# FPGA-7.net
KiCad netlist of a schematic drawn in Altium Designer
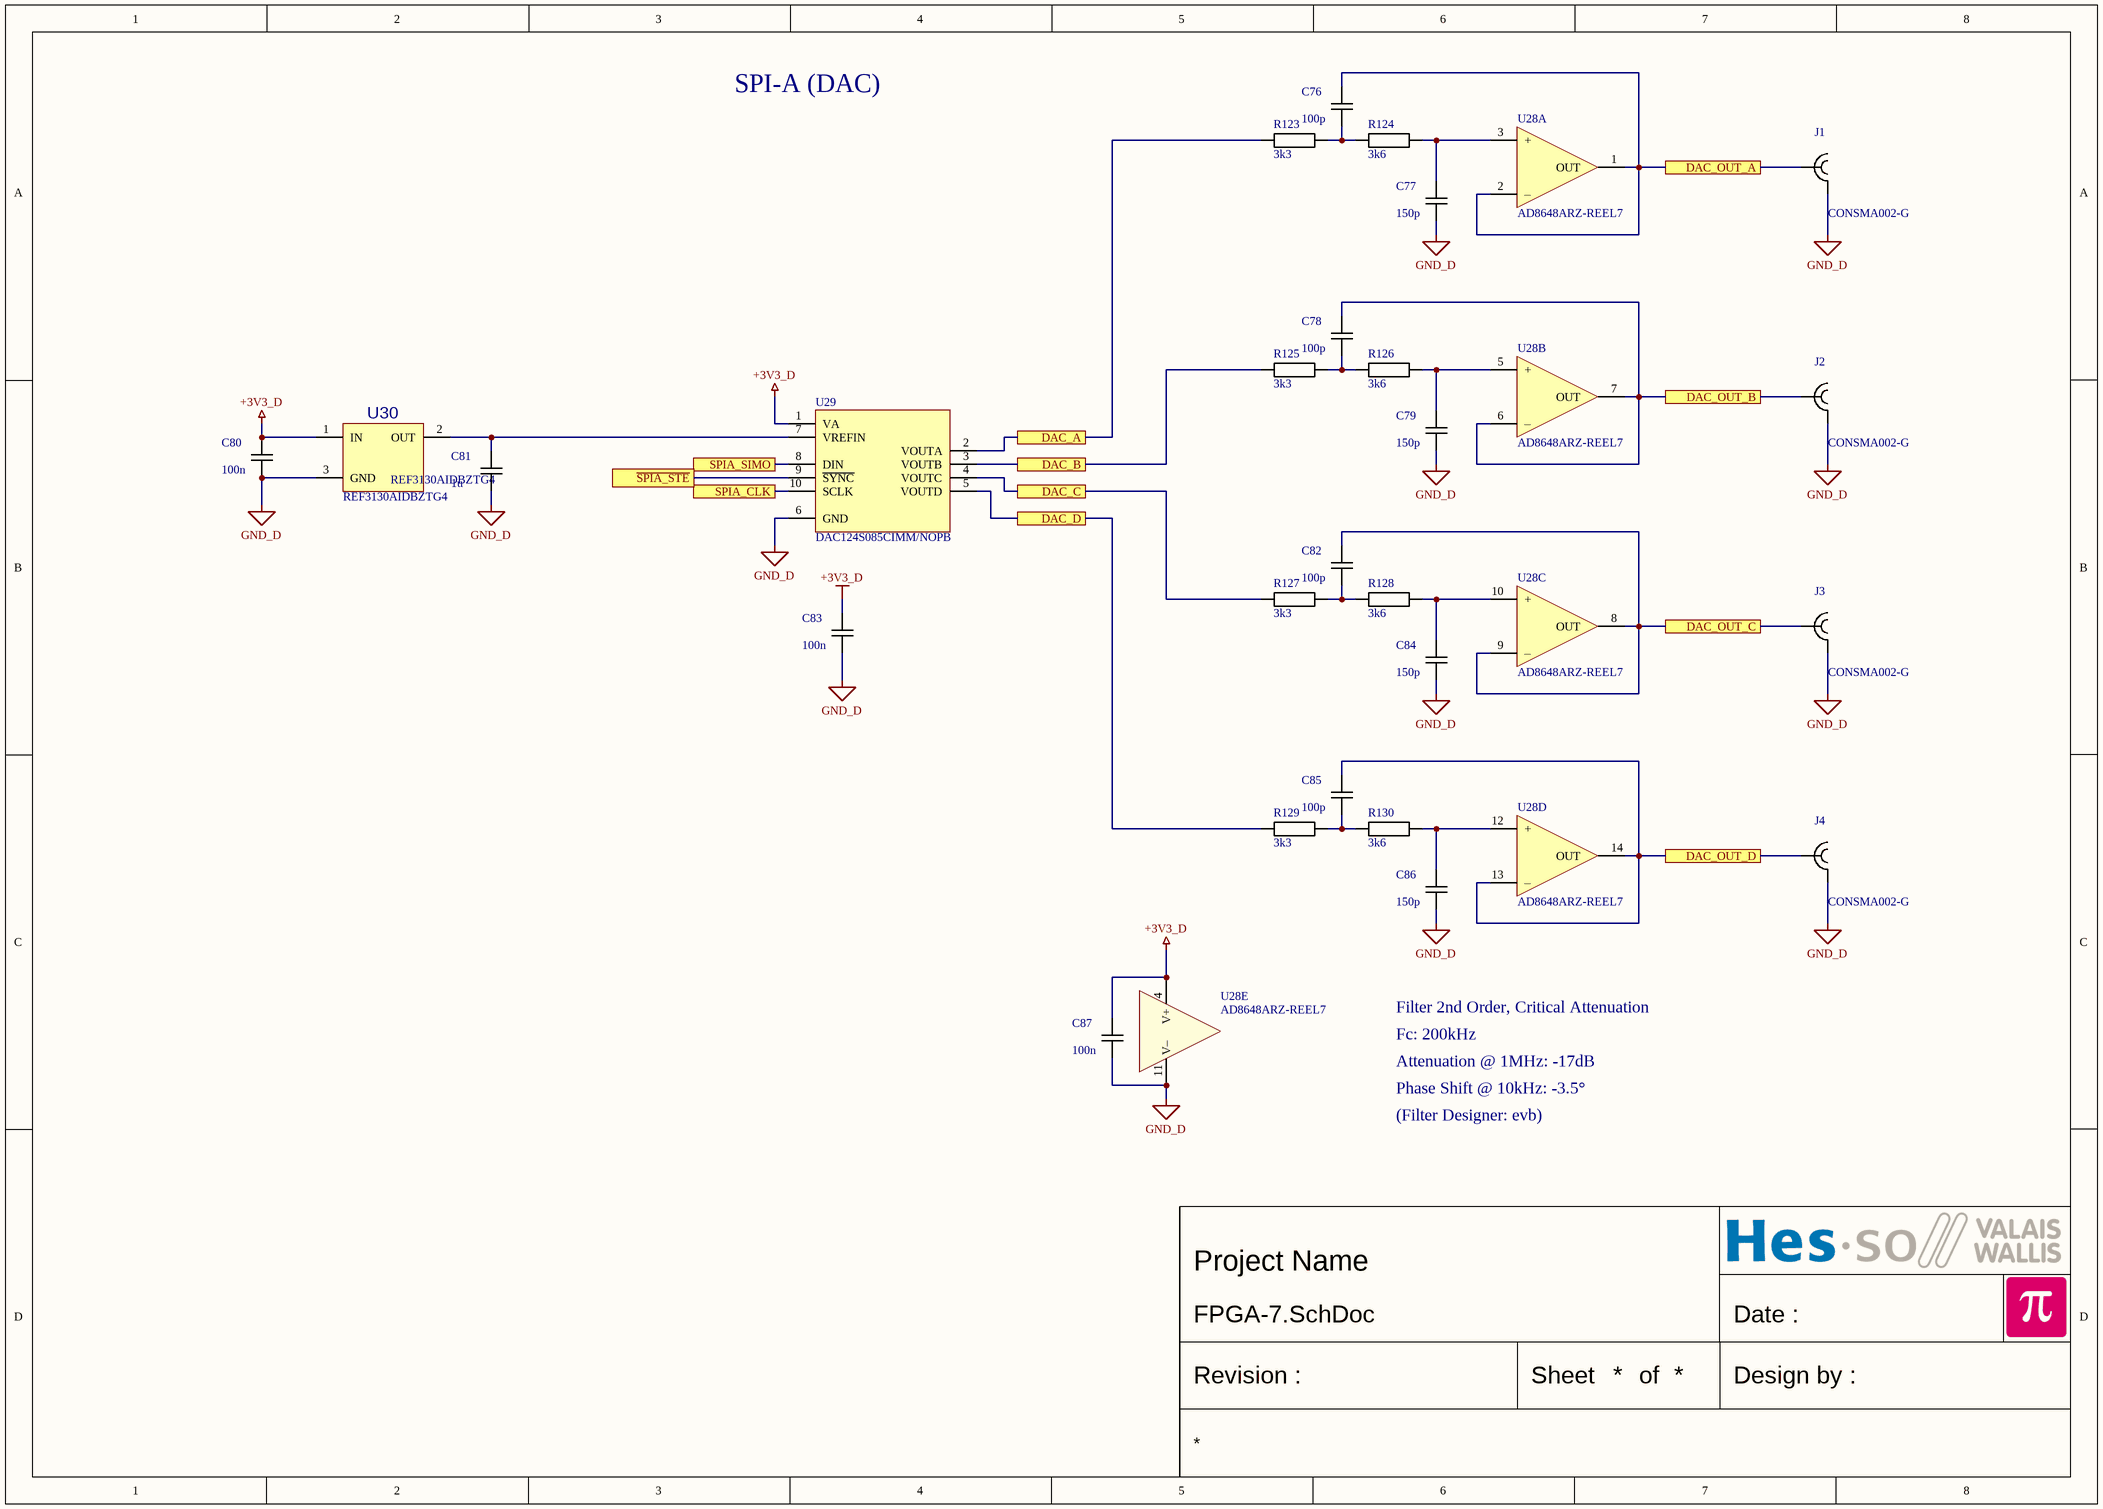
[diagram p0: FPGA-7.SchDoc]

(export (version "E")
  (design (tool "Eeschema 10.0.6"))
  (components
    (comp (ref "C76")
      (value "100p")
      (footprint "CAPACITOR 2012 REFLOW")
      (description "Capacitor X7R 10% 50V 2012(0805)")
      (libsource (lib "Capacitor") (part "Capacitor"))
    )
    (comp (ref "C77")
      (value "150p")
      (footprint "CAPACITOR 2012 REFLOW")
      (description "Capacitor X7R 10% 50V 2012(0805)")
      (libsource (lib "Capacitor") (part "Capacitor"))
    )
    (comp (ref "C78")
      (value "100p")
      (footprint "CAPACITOR 2012 REFLOW")
      (description "Capacitor X7R 10% 50V 2012(0805)")
      (libsource (lib "Capacitor") (part "Capacitor"))
    )
    (comp (ref "C79")
      (value "150p")
      (footprint "CAPACITOR 2012 REFLOW")
      (description "Capacitor X7R 10% 50V 2012(0805)")
      (libsource (lib "Capacitor") (part "Capacitor"))
    )
    (comp (ref "C80")
      (value "100n")
      (footprint "CAPACITOR 2012 REFLOW")
      (description "Capacitor X7R 10% 50V 2012(0805)")
      (libsource (lib "Capacitor") (part "Capacitor"))
    )
    (comp (ref "C81")
      (value "1u")
      (footprint "CAPACITOR 2012 REFLOW")
      (description "Capacitor X7R 10% 10V 2012(0805)")
      (libsource (lib "Capacitor") (part "Capacitor"))
    )
    (comp (ref "C82")
      (value "100p")
      (footprint "CAPACITOR 2012 REFLOW")
      (description "Capacitor X7R 10% 50V 2012(0805)")
      (libsource (lib "Capacitor") (part "Capacitor"))
    )
    (comp (ref "C83")
      (value "100n")
      (footprint "CAPACITOR 1608 REFLOW")
      (description "Capacitor X7R 10% 50V 1608(0603)")
      (libsource (lib "Capacitor") (part "Capacitor"))
    )
    (comp (ref "C84")
      (value "150p")
      (footprint "CAPACITOR 2012 REFLOW")
      (description "Capacitor X7R 10% 50V 2012(0805)")
      (libsource (lib "Capacitor") (part "Capacitor"))
    )
    (comp (ref "C85")
      (value "100p")
      (footprint "CAPACITOR 2012 REFLOW")
      (description "Capacitor X7R 10% 50V 2012(0805)")
      (libsource (lib "Capacitor") (part "Capacitor"))
    )
    (comp (ref "C86")
      (value "150p")
      (footprint "CAPACITOR 2012 REFLOW")
      (description "Capacitor X7R 10% 50V 2012(0805)")
      (libsource (lib "Capacitor") (part "Capacitor"))
    )
    (comp (ref "C87")
      (value "100n")
      (footprint "CAPACITOR 1608 REFLOW")
      (description "Capacitor X7R 10% 50V 1608(0603)")
      (libsource (lib "Capacitor") (part "Capacitor"))
    )
    (comp (ref "J1")
      (value "CONSMA002-G")
      (footprint "SMA TH Right Angle Linx CONSMA002")
      (description "SMA TH RIGHT ANGLE LINX CONSMA002")
      (fields (field (name "MANUFACTURER") "Linx Technologies"))
      (libsource (lib "Connector") (part "SMA TH RIGHT ANGLE LINX CONSMA002"))
    )
    (comp (ref "J2")
      (value "CONSMA002-G")
      (footprint "SMA TH Right Angle Linx CONSMA002")
      (description "SMA TH RIGHT ANGLE LINX CONSMA002")
      (fields (field (name "MANUFACTURER") "Linx Technologies"))
      (libsource (lib "Connector") (part "SMA TH RIGHT ANGLE LINX CONSMA002"))
    )
    (comp (ref "J3")
      (value "CONSMA002-G")
      (footprint "SMA TH Right Angle Linx CONSMA002")
      (description "SMA TH RIGHT ANGLE LINX CONSMA002")
      (fields (field (name "MANUFACTURER") "Linx Technologies"))
      (libsource (lib "Connector") (part "SMA TH RIGHT ANGLE LINX CONSMA002"))
    )
    (comp (ref "J4")
      (value "CONSMA002-G")
      (footprint "SMA TH Right Angle Linx CONSMA002")
      (description "SMA TH RIGHT ANGLE LINX CONSMA002")
      (fields (field (name "MANUFACTURER") "Linx Technologies"))
      (libsource (lib "Connector") (part "SMA TH RIGHT ANGLE LINX CONSMA002"))
    )
    (comp (ref "R123")
      (value "3k3")
      (footprint "RESISTOR 2012 REFLOW")
      (description "Resistor 1% 50V 125mW 2012(0805)")
      (libsource (lib "Resistor") (part "Resistor"))
    )
    (comp (ref "R124")
      (value "3k6")
      (footprint "RESISTOR 2012 REFLOW")
      (description "Resistor 1% 50V 125mW 2012(0805)")
      (libsource (lib "Resistor") (part "Resistor"))
    )
    (comp (ref "R125")
      (value "3k3")
      (footprint "RESISTOR 2012 REFLOW")
      (description "Resistor 1% 50V 125mW 2012(0805)")
      (libsource (lib "Resistor") (part "Resistor"))
    )
    (comp (ref "R126")
      (value "3k6")
      (footprint "RESISTOR 2012 REFLOW")
      (description "Resistor 1% 50V 125mW 2012(0805)")
      (libsource (lib "Resistor") (part "Resistor"))
    )
    (comp (ref "R127")
      (value "3k3")
      (footprint "RESISTOR 2012 REFLOW")
      (description "Resistor 1% 50V 125mW 2012(0805)")
      (libsource (lib "Resistor") (part "Resistor"))
    )
    (comp (ref "R128")
      (value "3k6")
      (footprint "RESISTOR 2012 REFLOW")
      (description "Resistor 1% 50V 125mW 2012(0805)")
      (libsource (lib "Resistor") (part "Resistor"))
    )
    (comp (ref "R129")
      (value "3k3")
      (footprint "RESISTOR 2012 REFLOW")
      (description "Resistor 1% 50V 125mW 2012(0805)")
      (libsource (lib "Resistor") (part "Resistor"))
    )
    (comp (ref "R130")
      (value "3k6")
      (footprint "RESISTOR 2012 REFLOW")
      (description "Resistor 1% 50V 125mW 2012(0805)")
      (libsource (lib "Resistor") (part "Resistor"))
    )
    (comp (ref "U28")
      (value "AD8648ARZ-REEL7")
      (footprint "SO14 P1.27 C4.0X8.8 H1.75")
      (description "Generic quad OPA 14 pins")
      (fields (field (name "MANUFACTURER") "Analog Devices"))
      (libsource (lib "Amplifier") (part "OPA QUAD"))
    )
    (comp (ref "U29")
      (value "DAC124S085CIMM/NOPB")
      (footprint "VSSOP10 P0.5 C3.1X3.1 H1.1")
      (description "DAC124S085 12-Bit Micro Power Quad Digital-to-Analog Converter With Rail-to-Rail Output")
      (fields (field (name "MANUFACTURER") "Texas Instruments"))
      (libsource (lib "Converter") (part "DAC124S085CIMM"))
    )
    (comp (ref "U30")
      (value "REF3130AIDBZTG4")
      (footprint "SOT23 P0.95 C1.6x3.0 H1.3")
      (description "Generic Positive Voltage Reference")
      (fields
        (field (name "ALTIUM_VALUE") "REF3130AIDBZTG4")
        (field (name "MANUFACTURER") "Texas Instruments")
      )
      (libsource (lib "Regulator") (part "REFERENCE SOT23 IN-OUT- GND"))
    )
  )
  (nets
    (net (code "1") (name "+3V3_D") (class "Default")
      (node (ref "C80") (pin "2") (pinfunction "2_2") (pintype "passive"))
      (node (ref "C83") (pin "2") (pinfunction "2_2") (pintype "passive"))
      (node (ref "C87") (pin "2") (pinfunction "2_2") (pintype "passive"))
      (node (ref "U28") (pin "4") (pinfunction "V+_4") (pintype "passive"))
      (node (ref "U29") (pin "1") (pinfunction "VA_1") (pintype "passive"))
      (node (ref "U30") (pin "1") (pinfunction "IN_1") (pintype "passive"))
    )
    (net (code "2") (name "/DAC_A") (class "Default")
      (node (ref "R123") (pin "1") (pinfunction "1_1") (pintype "passive"))
      (node (ref "U29") (pin "2") (pinfunction "VOUTA_2") (pintype "passive"))
    )
    (net (code "3") (name "/DAC_B") (class "Default")
      (node (ref "R125") (pin "1") (pinfunction "1_1") (pintype "passive"))
      (node (ref "U29") (pin "3") (pinfunction "VOUTB_3") (pintype "passive"))
    )
    (net (code "4") (name "/DAC_C") (class "Default")
      (node (ref "R127") (pin "1") (pinfunction "1_1") (pintype "passive"))
      (node (ref "U29") (pin "4") (pinfunction "VOUTC_4") (pintype "passive"))
    )
    (net (code "5") (name "/DAC_D") (class "Default")
      (node (ref "R129") (pin "1") (pinfunction "1_1") (pintype "passive"))
      (node (ref "U29") (pin "5") (pinfunction "VOUTD_5") (pintype "passive"))
    )
    (net (code "6") (name "/DAC_OUT_A") (class "Default")
      (node (ref "C76") (pin "2") (pinfunction "2_2") (pintype "passive"))
      (node (ref "J1") (pin "1") (pinfunction "1_1") (pintype "passive"))
      (node (ref "U28") (pin "1") (pinfunction "OUT_1") (pintype "passive"))
      (node (ref "U28") (pin "2") (pinfunction "–_2") (pintype "passive"))
    )
    (net (code "7") (name "/DAC_OUT_B") (class "Default")
      (node (ref "C78") (pin "2") (pinfunction "2_2") (pintype "passive"))
      (node (ref "J2") (pin "1") (pinfunction "1_1") (pintype "passive"))
      (node (ref "U28") (pin "6") (pinfunction "–_6") (pintype "passive"))
      (node (ref "U28") (pin "7") (pinfunction "OUT_7") (pintype "passive"))
    )
    (net (code "8") (name "/DAC_OUT_C") (class "Default")
      (node (ref "C82") (pin "2") (pinfunction "2_2") (pintype "passive"))
      (node (ref "J3") (pin "1") (pinfunction "1_1") (pintype "passive"))
      (node (ref "U28") (pin "8") (pinfunction "OUT_8") (pintype "passive"))
      (node (ref "U28") (pin "9") (pinfunction "–_9") (pintype "passive"))
    )
    (net (code "9") (name "/DAC_OUT_D") (class "Default")
      (node (ref "C85") (pin "2") (pinfunction "2_2") (pintype "passive"))
      (node (ref "J4") (pin "1") (pinfunction "1_1") (pintype "passive"))
      (node (ref "U28") (pin "13") (pinfunction "–_13") (pintype "passive"))
      (node (ref "U28") (pin "14") (pinfunction "OUT_14") (pintype "passive"))
    )
    (net (code "10") (name "/SPIA_CLK") (class "Default")
      (node (ref "U29") (pin "10") (pinfunction "SCLK_10") (pintype "passive"))
    )
    (net (code "11") (name "/SPIA_SIMO") (class "Default")
      (node (ref "U29") (pin "8") (pinfunction "DIN_8") (pintype "passive"))
    )
    (net (code "12") (name "/~{SPIA_STE}") (class "Default")
      (node (ref "U29") (pin "9") (pinfunction "~{SYNC}_9") (pintype "passive"))
    )
    (net (code "13") (name "GND_D") (class "Default")
      (node (ref "C77") (pin "1") (pinfunction "1_1") (pintype "passive"))
      (node (ref "C79") (pin "1") (pinfunction "1_1") (pintype "passive"))
      (node (ref "C80") (pin "1") (pinfunction "1_1") (pintype "passive"))
      (node (ref "C81") (pin "1") (pinfunction "1_1") (pintype "passive"))
      (node (ref "C83") (pin "1") (pinfunction "1_1") (pintype "passive"))
      (node (ref "C84") (pin "1") (pinfunction "1_1") (pintype "passive"))
      (node (ref "C86") (pin "1") (pinfunction "1_1") (pintype "passive"))
      (node (ref "C87") (pin "1") (pinfunction "1_1") (pintype "passive"))
      (node (ref "J1") (pin "2") (pinfunction "2_2") (pintype "passive"))
      (node (ref "J2") (pin "2") (pinfunction "2_2") (pintype "passive"))
      (node (ref "J3") (pin "2") (pinfunction "2_2") (pintype "passive"))
      (node (ref "J4") (pin "2") (pinfunction "2_2") (pintype "passive"))
      (node (ref "U28") (pin "11") (pinfunction "V–_11") (pintype "passive"))
      (node (ref "U29") (pin "6") (pinfunction "GND_6") (pintype "passive"))
      (node (ref "U30") (pin "3") (pinfunction "GND_3") (pintype "passive"))
    )
    (net (code "14") (name "Net-(C76-Pad1)") (class "Default")
      (node (ref "C76") (pin "1") (pinfunction "1_1") (pintype "passive"))
      (node (ref "R123") (pin "2") (pinfunction "2_2") (pintype "passive"))
      (node (ref "R124") (pin "1") (pinfunction "1_1") (pintype "passive"))
    )
    (net (code "15") (name "Net-(C78-Pad1)") (class "Default")
      (node (ref "C78") (pin "1") (pinfunction "1_1") (pintype "passive"))
      (node (ref "R125") (pin "2") (pinfunction "2_2") (pintype "passive"))
      (node (ref "R126") (pin "1") (pinfunction "1_1") (pintype "passive"))
    )
    (net (code "16") (name "Net-(C82-Pad1)") (class "Default")
      (node (ref "C82") (pin "1") (pinfunction "1_1") (pintype "passive"))
      (node (ref "R127") (pin "2") (pinfunction "2_2") (pintype "passive"))
      (node (ref "R128") (pin "1") (pinfunction "1_1") (pintype "passive"))
    )
    (net (code "17") (name "Net-(C85-Pad1)") (class "Default")
      (node (ref "C85") (pin "1") (pinfunction "1_1") (pintype "passive"))
      (node (ref "R129") (pin "2") (pinfunction "2_2") (pintype "passive"))
      (node (ref "R130") (pin "1") (pinfunction "1_1") (pintype "passive"))
    )
    (net (code "18") (name "Net-(U28A-+)") (class "Default")
      (node (ref "C77") (pin "2") (pinfunction "2_2") (pintype "passive"))
      (node (ref "R124") (pin "2") (pinfunction "2_2") (pintype "passive"))
      (node (ref "U28") (pin "3") (pinfunction "+_3") (pintype "passive"))
    )
    (net (code "19") (name "Net-(U28B-+)") (class "Default")
      (node (ref "C79") (pin "2") (pinfunction "2_2") (pintype "passive"))
      (node (ref "R126") (pin "2") (pinfunction "2_2") (pintype "passive"))
      (node (ref "U28") (pin "5") (pinfunction "+_5") (pintype "passive"))
    )
    (net (code "20") (name "Net-(U28C-+)") (class "Default")
      (node (ref "C84") (pin "2") (pinfunction "2_2") (pintype "passive"))
      (node (ref "R128") (pin "2") (pinfunction "2_2") (pintype "passive"))
      (node (ref "U28") (pin "10") (pinfunction "+_10") (pintype "passive"))
    )
    (net (code "21") (name "Net-(U28D-+)") (class "Default")
      (node (ref "C86") (pin "2") (pinfunction "2_2") (pintype "passive"))
      (node (ref "R130") (pin "2") (pinfunction "2_2") (pintype "passive"))
      (node (ref "U28") (pin "12") (pinfunction "+_12") (pintype "passive"))
    )
    (net (code "22") (name "Net-(U29-VREFIN)") (class "Default")
      (node (ref "C81") (pin "2") (pinfunction "2_2") (pintype "passive"))
      (node (ref "U29") (pin "7") (pinfunction "VREFIN_7") (pintype "passive"))
      (node (ref "U30") (pin "2") (pinfunction "OUT_2") (pintype "passive"))
    )
  )
)
